# S5D3_MCU_only.net
KiCad netlist of a schematic drawn in EAGLE
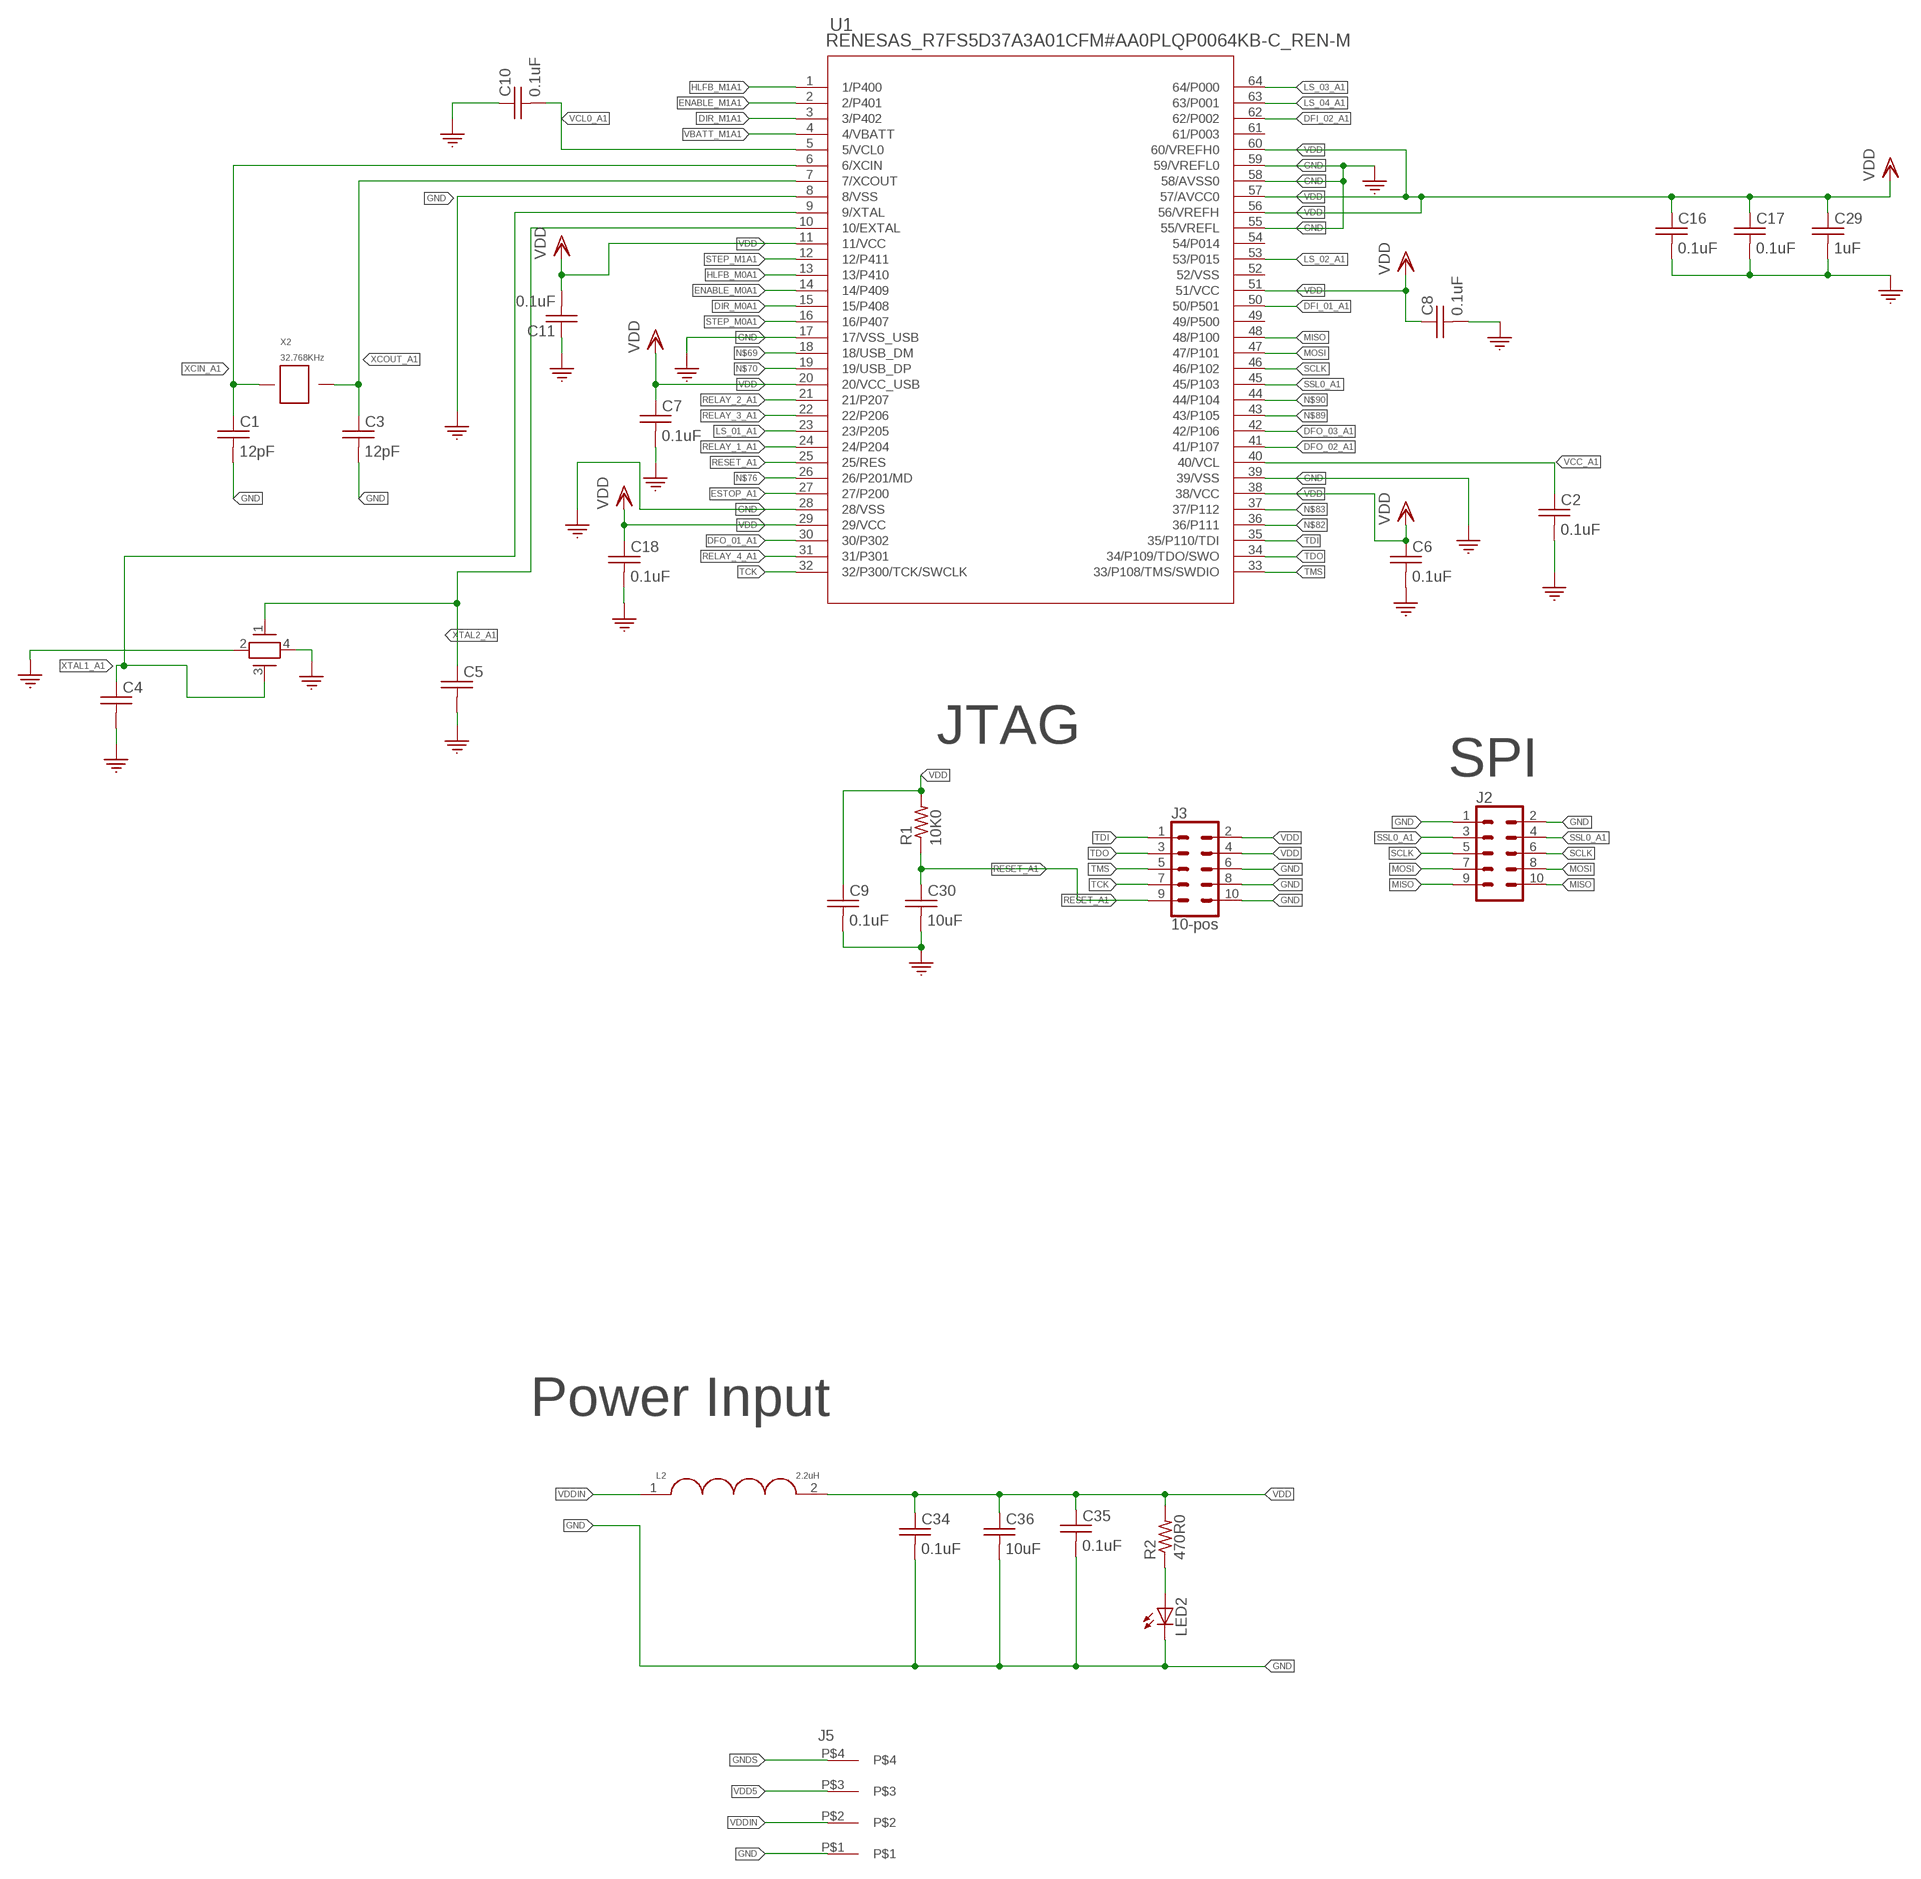
[diagram p0: schematic, sheet 1]

(export (version "E")
  (design (tool "Eeschema 10.0.6"))
  (components
    (comp (ref "C1")
      (value "12pF")
      (footprint "eagle-import:0402")
      (fields (field (name "PARTNO") "CL05C120JB5NNNC"))
      (libsource (lib "eagle-import") (part "C_0402_12PF"))
    )
    (comp (ref "C2")
      (value "0.1uF")
      (footprint "eagle-import:0402")
      (fields (field (name "PARTNO") "CL05F104ZO5NNNC"))
      (libsource (lib "eagle-import") (part "C_0402_0.1UF"))
    )
    (comp (ref "C3")
      (value "12pF")
      (footprint "eagle-import:0402")
      (fields (field (name "PARTNO") "CL05C120JB5NNNC"))
      (libsource (lib "eagle-import") (part "C_0402_12PF"))
    )
    (comp (ref "C4")
      (value "10pF")
      (footprint "eagle-import:0402")
      (fields (field (name "PARTNO") "CC0402JRNPO9BN100"))
      (libsource (lib "eagle-import") (part "C_0402_10PF"))
    )
    (comp (ref "C5")
      (value "10pF")
      (footprint "eagle-import:0402")
      (fields (field (name "PARTNO") "CC0402JRNPO9BN100"))
      (libsource (lib "eagle-import") (part "C_0402_10PF"))
    )
    (comp (ref "C6")
      (value "0.1uF")
      (footprint "eagle-import:0402")
      (fields (field (name "PARTNO") "CL05F104ZO5NNNC"))
      (libsource (lib "eagle-import") (part "C_0402_0.1UF"))
    )
    (comp (ref "C7")
      (value "0.1uF")
      (footprint "eagle-import:0402")
      (fields (field (name "PARTNO") "CL05F104ZO5NNNC"))
      (libsource (lib "eagle-import") (part "C_0402_0.1UF"))
    )
    (comp (ref "C8")
      (value "0.1uF")
      (footprint "eagle-import:0402")
      (fields (field (name "PARTNO") "CL05F104ZO5NNNC"))
      (libsource (lib "eagle-import") (part "C_0402_0.1UF"))
    )
    (comp (ref "C9")
      (value "0.1uF")
      (footprint "eagle-import:0402")
      (fields (field (name "PARTNO") "CL05F104ZO5NNNC"))
      (libsource (lib "eagle-import") (part "C_0402_0.1UF"))
    )
    (comp (ref "C10")
      (value "0.1uF")
      (footprint "eagle-import:0402")
      (fields (field (name "PARTNO") "CL05F104ZO5NNNC"))
      (libsource (lib "eagle-import") (part "C_0402_0.1UF"))
    )
    (comp (ref "C11")
      (value "0.1uF")
      (footprint "eagle-import:0402")
      (fields (field (name "PARTNO") "CL05F104ZO5NNNC"))
      (libsource (lib "eagle-import") (part "C_0402_0.1UF"))
    )
    (comp (ref "C16")
      (value "0.1uF")
      (footprint "eagle-import:0402")
      (fields (field (name "PARTNO") "CL05F104ZO5NNNC"))
      (libsource (lib "eagle-import") (part "C_0402_0.1UF"))
    )
    (comp (ref "C17")
      (value "0.1uF")
      (footprint "eagle-import:0402")
      (fields (field (name "PARTNO") "CL05F104ZO5NNNC"))
      (libsource (lib "eagle-import") (part "C_0402_0.1UF"))
    )
    (comp (ref "C18")
      (value "0.1uF")
      (footprint "eagle-import:0402")
      (fields (field (name "PARTNO") "CL05F104ZO5NNNC"))
      (libsource (lib "eagle-import") (part "C_0402_0.1UF"))
    )
    (comp (ref "C29")
      (value "1uF")
      (footprint "eagle-import:0402")
      (fields (field (name "PARTNO") "CL05A105KO5NNNC"))
      (libsource (lib "eagle-import") (part "C_0402_1UF"))
    )
    (comp (ref "C30")
      (value "10uF")
      (footprint "eagle-import:0402")
      (fields (field (name "PARTNO") "CL05A106MP8NUB8"))
      (libsource (lib "eagle-import") (part "C_0402_10UF"))
    )
    (comp (ref "C34")
      (value "0.1uF")
      (footprint "eagle-import:0402")
      (fields (field (name "PARTNO") "CL05F104ZO5NNNC"))
      (libsource (lib "eagle-import") (part "C_0402_0.1UF"))
    )
    (comp (ref "C35")
      (value "0.1uF")
      (footprint "eagle-import:0402")
      (fields (field (name "PARTNO") "CL05F104ZO5NNNC"))
      (libsource (lib "eagle-import") (part "C_0402_0.1UF"))
    )
    (comp (ref "C36")
      (value "10uF")
      (footprint "eagle-import:0402")
      (fields (field (name "PARTNO") "CL05A106MP8NUB8"))
      (libsource (lib "eagle-import") (part "C_0402_10UF"))
    )
    (comp (ref "J2")
      (value "CONN_05X2PTH")
      (footprint "eagle-import:2X5")
      (libsource (lib "eagle-import") (part "CONN_05X2PTH"))
    )
    (comp (ref "J3")
      (value "10-pos")
      (footprint "eagle-import:2X5")
      (fields (field (name "PARTNO") "PH2RA-10-UA"))
      (libsource (lib "eagle-import") (part "CONN_05X2_RAPTH"))
    )
    (comp (ref "J5")
      (value "4-pos")
      (footprint "eagle-import:1X4_3.81MM_PITCH")
      (fields (field (name "PARTNO") "691322310004"))
      (libsource (lib "eagle-import") (part "3.81MM_1_X_4_RT_ANGLE_PLUG_HEADER"))
    )
    (comp (ref "L2")
      (value "2.2uH")
      (footprint "eagle-import:1008")
      (fields (field (name "PARTNO") "LQM2HPN2R2MG0L"))
      (libsource (lib "eagle-import") (part "INDUCTOR_1008_2.2_MH_1.3A"))
    )
    (comp (ref "LED2")
      (value "Green")
      (footprint "eagle-import:0805")
      (fields (field (name "PARTNO") "LG R971-KN-1"))
      (libsource (lib "eagle-import") (part "LED_0805_GREEN"))
    )
    (comp (ref "R1")
      (value "10K0")
      (footprint "eagle-import:0402")
      (fields (field (name "PARTNO") "RMCF0402JT10K0"))
      (libsource (lib "eagle-import") (part "R_0402_10K0"))
    )
    (comp (ref "R2")
      (value "470R0")
      (footprint "eagle-import:0402")
      (fields (field (name "PARTNO") "RMCF0402JT470R"))
      (libsource (lib "eagle-import") (part "R_0402_470R0"))
    )
    (comp (ref "U1")
      (value "RENESAS_R7FS5D37A3A01CFM#AA0PLQP0064KB-C_REN-M")
      (footprint "eagle-import:PLQP0064KB-C_REN-M")
      (fields
        (field (name "PARTNO") "R7FS3A37A3A01CFM#AA0")
        (field (name "COPYRIGHT") "Copyright (C) 2023 Ultra Librarian. All rights reserved.")
      )
      (libsource (lib "eagle-import") (part "RENESAS_R7FS5D37A3A01CFM#AA0PLQP0064KB-C_REN-M"))
    )
    (comp (ref "X2")
      (value "32.768KHz")
      (footprint "eagle-import:SMD_X_2_PADS")
      (fields (field (name "PARTNO") "ABS07-32.768KHZ-T"))
      (libsource (lib "eagle-import") (part "XTAL_32.768KHZ"))
    )
    (comp (ref "Y1")
      (value "XTAL_12MHZ_ABM8G-12.000MHZ-B4Y-T")
      (footprint "eagle-import:CRYSTAL_ABM8G_ABR")
      (fields
        (field (name "PARTNO") "ABM8G-12.000MHZ-B4Y-T")
        (field (name "COPYRIGHT") "Copyright (C) 2023 Ultra Librarian. All rights reserved.")
      )
      (libsource (lib "eagle-import") (part "XTAL_12MHZ_ABM8G-12.000MHZ-B4Y-T"))
    )
  )
  (nets
    (net (code "1") (name "DFI_01_A1") (class "Default")
      (node (ref "U1") (pin "50") (pinfunction "50/P501_50") (pintype "bidirectional"))
    )
    (net (code "2") (name "DFI_02_A1") (class "Default")
      (node (ref "U1") (pin "62") (pinfunction "62/P002_62") (pintype "bidirectional"))
    )
    (net (code "3") (name "DFO_01_A1") (class "Default")
      (node (ref "U1") (pin "30") (pinfunction "30/P302_30") (pintype "bidirectional"))
    )
    (net (code "4") (name "DFO_02_A1") (class "Default")
      (node (ref "U1") (pin "41") (pinfunction "41/P107_41") (pintype "bidirectional"))
    )
    (net (code "5") (name "DFO_03_A1") (class "Default")
      (node (ref "U1") (pin "42") (pinfunction "42/P106_42") (pintype "bidirectional"))
    )
    (net (code "6") (name "DIR_M0A1") (class "Default")
      (node (ref "U1") (pin "15") (pinfunction "15/P408_15") (pintype "bidirectional"))
    )
    (net (code "7") (name "DIR_M1A1") (class "Default")
      (node (ref "U1") (pin "3") (pinfunction "3/P402_3") (pintype "bidirectional"))
    )
    (net (code "8") (name "ENABLE_M0A1") (class "Default")
      (node (ref "U1") (pin "14") (pinfunction "14/P409_14") (pintype "bidirectional"))
    )
    (net (code "9") (name "ENABLE_M1A1") (class "Default")
      (node (ref "U1") (pin "2") (pinfunction "2/P401_2") (pintype "bidirectional"))
    )
    (net (code "10") (name "ESTOP_A1") (class "Default")
      (node (ref "U1") (pin "27") (pinfunction "27/P200_27") (pintype "bidirectional"))
    )
    (net (code "11") (name "GND") (class "Default")
      (node (ref "C1") (pin "P$2") (pinfunction "2_P$2") (pintype "passive"))
      (node (ref "C10") (pin "P$1") (pinfunction "1_P$1") (pintype "passive"))
      (node (ref "C11") (pin "P$1") (pinfunction "1_P$1") (pintype "passive"))
      (node (ref "C16") (pin "P$2") (pinfunction "2_P$2") (pintype "passive"))
      (node (ref "C17") (pin "P$2") (pinfunction "2_P$2") (pintype "passive"))
      (node (ref "C18") (pin "P$2") (pinfunction "2_P$2") (pintype "passive"))
      (node (ref "C2") (pin "P$2") (pinfunction "2_P$2") (pintype "passive"))
      (node (ref "C29") (pin "P$2") (pinfunction "2_P$2") (pintype "passive"))
      (node (ref "C3") (pin "P$2") (pinfunction "2_P$2") (pintype "passive"))
      (node (ref "C30") (pin "P$2") (pinfunction "2_P$2") (pintype "passive"))
      (node (ref "C34") (pin "P$2") (pinfunction "2_P$2") (pintype "passive"))
      (node (ref "C35") (pin "P$2") (pinfunction "2_P$2") (pintype "passive"))
      (node (ref "C36") (pin "P$2") (pinfunction "2_P$2") (pintype "passive"))
      (node (ref "C4") (pin "P$2") (pinfunction "2_P$2") (pintype "passive"))
      (node (ref "C5") (pin "P$2") (pinfunction "2_P$2") (pintype "passive"))
      (node (ref "C6") (pin "P$2") (pinfunction "2_P$2") (pintype "passive"))
      (node (ref "C7") (pin "P$2") (pinfunction "2_P$2") (pintype "passive"))
      (node (ref "C8") (pin "P$2") (pinfunction "2_P$2") (pintype "passive"))
      (node (ref "C9") (pin "P$2") (pinfunction "2_P$2") (pintype "passive"))
      (node (ref "J2") (pin "1") (pinfunction "1_1") (pintype "passive"))
      (node (ref "J2") (pin "2") (pinfunction "2_2") (pintype "passive"))
      (node (ref "J3") (pin "10") (pinfunction "10_10") (pintype "passive"))
      (node (ref "J3") (pin "6") (pinfunction "6_6") (pintype "passive"))
      (node (ref "J3") (pin "8") (pinfunction "8_8") (pintype "passive"))
      (node (ref "J5") (pin "P$1") (pinfunction "P$1_P$1") (pintype "bidirectional"))
      (node (ref "LED2") (pin "2") (pinfunction "C_2") (pintype "passive"))
      (node (ref "U1") (pin "17") (pinfunction "17/VSS_USB_17") (pintype "power_in"))
      (node (ref "U1") (pin "28") (pinfunction "28/VSS_28") (pintype "bidirectional"))
      (node (ref "U1") (pin "39") (pinfunction "39/VSS_39") (pintype "power_in"))
      (node (ref "U1") (pin "55") (pinfunction "55/VREFL_55") (pintype "bidirectional"))
      (node (ref "U1") (pin "58") (pinfunction "58/AVSS0_58") (pintype "bidirectional"))
      (node (ref "U1") (pin "59") (pinfunction "59/VREFL0_59") (pintype "bidirectional"))
      (node (ref "U1") (pin "8") (pinfunction "8/VSS_8") (pintype "power_in"))
      (node (ref "Y1") (pin "2") (pinfunction "2_2") (pintype "passive"))
      (node (ref "Y1") (pin "4") (pinfunction "4_4") (pintype "passive"))
    )
    (net (code "12") (name "GNDS") (class "Default")
      (node (ref "J5") (pin "P$4") (pinfunction "P$4_P$4") (pintype "bidirectional"))
    )
    (net (code "13") (name "HLFB_M0A1") (class "Default")
      (node (ref "U1") (pin "13") (pinfunction "13/P410_13") (pintype "bidirectional"))
    )
    (net (code "14") (name "HLFB_M1A1") (class "Default")
      (node (ref "U1") (pin "1") (pinfunction "1/P400_1") (pintype "bidirectional"))
    )
    (net (code "15") (name "LS_01_A1") (class "Default")
      (node (ref "U1") (pin "23") (pinfunction "23/P205_23") (pintype "bidirectional"))
    )
    (net (code "16") (name "LS_02_A1") (class "Default")
      (node (ref "U1") (pin "53") (pinfunction "53/P015_53") (pintype "bidirectional"))
    )
    (net (code "17") (name "LS_03_A1") (class "Default")
      (node (ref "U1") (pin "64") (pinfunction "64/P000_64") (pintype "bidirectional"))
    )
    (net (code "18") (name "LS_04_A1") (class "Default")
      (node (ref "U1") (pin "63") (pinfunction "63/P001_63") (pintype "bidirectional"))
    )
    (net (code "19") (name "MISO") (class "Default")
      (node (ref "J2") (pin "10") (pinfunction "10_10") (pintype "passive"))
      (node (ref "J2") (pin "9") (pinfunction "9_9") (pintype "passive"))
      (node (ref "U1") (pin "48") (pinfunction "48/P100_48") (pintype "bidirectional"))
    )
    (net (code "20") (name "MOSI") (class "Default")
      (node (ref "J2") (pin "7") (pinfunction "7_7") (pintype "passive"))
      (node (ref "J2") (pin "8") (pinfunction "8_8") (pintype "passive"))
      (node (ref "U1") (pin "47") (pinfunction "47/P101_47") (pintype "bidirectional"))
    )
    (net (code "21") (name "N$69") (class "Default")
      (node (ref "U1") (pin "18") (pinfunction "18/USB_DM_18") (pintype "bidirectional"))
    )
    (net (code "22") (name "N$70") (class "Default")
      (node (ref "U1") (pin "19") (pinfunction "19/USB_DP_19") (pintype "bidirectional"))
    )
    (net (code "23") (name "N$76") (class "Default")
      (node (ref "U1") (pin "26") (pinfunction "26/P201/MD_26") (pintype "bidirectional"))
    )
    (net (code "24") (name "N$82") (class "Default")
      (node (ref "U1") (pin "36") (pinfunction "36/P111_36") (pintype "bidirectional"))
    )
    (net (code "25") (name "N$83") (class "Default")
      (node (ref "U1") (pin "37") (pinfunction "37/P112_37") (pintype "bidirectional"))
    )
    (net (code "26") (name "N$89") (class "Default")
      (node (ref "U1") (pin "43") (pinfunction "43/P105_43") (pintype "bidirectional"))
    )
    (net (code "27") (name "N$90") (class "Default")
      (node (ref "U1") (pin "44") (pinfunction "44/P104_44") (pintype "bidirectional"))
    )
    (net (code "28") (name "Net-(LED2-A)") (class "Default")
      (node (ref "LED2") (pin "1") (pinfunction "A_1") (pintype "passive"))
      (node (ref "R2") (pin "P$1") (pinfunction "1_P$1") (pintype "passive"))
    )
    (net (code "29") (name "RELAY_1_A1") (class "Default")
      (node (ref "U1") (pin "24") (pinfunction "24/P204_24") (pintype "bidirectional"))
    )
    (net (code "30") (name "RELAY_2_A1") (class "Default")
      (node (ref "U1") (pin "21") (pinfunction "21/P207_21") (pintype "power_in"))
    )
    (net (code "31") (name "RELAY_3_A1") (class "Default")
      (node (ref "U1") (pin "22") (pinfunction "22/P206_22") (pintype "bidirectional"))
    )
    (net (code "32") (name "RELAY_4_A1") (class "Default")
      (node (ref "U1") (pin "31") (pinfunction "31/P301_31") (pintype "bidirectional"))
    )
    (net (code "33") (name "RESET_A1") (class "Default")
      (node (ref "C30") (pin "P$1") (pinfunction "1_P$1") (pintype "passive"))
      (node (ref "J3") (pin "9") (pinfunction "9_9") (pintype "passive"))
      (node (ref "R1") (pin "P$1") (pinfunction "1_P$1") (pintype "passive"))
      (node (ref "U1") (pin "25") (pinfunction "25/RES_25") (pintype "input"))
    )
    (net (code "34") (name "SCLK") (class "Default")
      (node (ref "J2") (pin "5") (pinfunction "5_5") (pintype "passive"))
      (node (ref "J2") (pin "6") (pinfunction "6_6") (pintype "passive"))
      (node (ref "U1") (pin "46") (pinfunction "46/P102_46") (pintype "bidirectional"))
    )
    (net (code "35") (name "SSL0_A1") (class "Default")
      (node (ref "J2") (pin "3") (pinfunction "3_3") (pintype "passive"))
      (node (ref "J2") (pin "4") (pinfunction "4_4") (pintype "passive"))
      (node (ref "U1") (pin "45") (pinfunction "45/P103_45") (pintype "bidirectional"))
    )
    (net (code "36") (name "STEP_M0A1") (class "Default")
      (node (ref "U1") (pin "16") (pinfunction "16/P407_16") (pintype "bidirectional"))
    )
    (net (code "37") (name "STEP_M1A1") (class "Default")
      (node (ref "U1") (pin "12") (pinfunction "12/P411_12") (pintype "bidirectional"))
    )
    (net (code "38") (name "TCK") (class "Default")
      (node (ref "J3") (pin "7") (pinfunction "7_7") (pintype "passive"))
      (node (ref "U1") (pin "32") (pinfunction "32/P300/TCK/SWCLK_32") (pintype "bidirectional"))
    )
    (net (code "39") (name "TDI") (class "Default")
      (node (ref "J3") (pin "1") (pinfunction "1_1") (pintype "passive"))
      (node (ref "U1") (pin "35") (pinfunction "35/P110/TDI_35") (pintype "bidirectional"))
    )
    (net (code "40") (name "TDO") (class "Default")
      (node (ref "J3") (pin "3") (pinfunction "3_3") (pintype "passive"))
      (node (ref "U1") (pin "34") (pinfunction "34/P109/TDO/SWO_34") (pintype "bidirectional"))
    )
    (net (code "41") (name "TMS") (class "Default")
      (node (ref "J3") (pin "5") (pinfunction "5_5") (pintype "passive"))
      (node (ref "U1") (pin "33") (pinfunction "33/P108/TMS/SWDIO_33") (pintype "bidirectional"))
    )
    (net (code "42") (name "VBATT_M1A1") (class "Default")
      (node (ref "U1") (pin "4") (pinfunction "4/VBATT_4") (pintype "power_in"))
    )
    (net (code "43") (name "VCC_A1") (class "Default")
      (node (ref "C2") (pin "P$1") (pinfunction "1_P$1") (pintype "passive"))
      (node (ref "U1") (pin "40") (pinfunction "40/VCL_40") (pintype "power_in"))
    )
    (net (code "44") (name "VCL0_A1") (class "Default")
      (node (ref "C10") (pin "P$2") (pinfunction "2_P$2") (pintype "passive"))
      (node (ref "U1") (pin "5") (pinfunction "5/VCL0_5") (pintype "power_in"))
    )
    (net (code "45") (name "VDD") (class "Default")
      (node (ref "C11") (pin "P$2") (pinfunction "2_P$2") (pintype "passive"))
      (node (ref "C16") (pin "P$1") (pinfunction "1_P$1") (pintype "passive"))
      (node (ref "C17") (pin "P$1") (pinfunction "1_P$1") (pintype "passive"))
      (node (ref "C18") (pin "P$1") (pinfunction "1_P$1") (pintype "passive"))
      (node (ref "C29") (pin "P$1") (pinfunction "1_P$1") (pintype "passive"))
      (node (ref "C34") (pin "P$1") (pinfunction "1_P$1") (pintype "passive"))
      (node (ref "C35") (pin "P$1") (pinfunction "1_P$1") (pintype "passive"))
      (node (ref "C36") (pin "P$1") (pinfunction "1_P$1") (pintype "passive"))
      (node (ref "C6") (pin "P$1") (pinfunction "1_P$1") (pintype "passive"))
      (node (ref "C7") (pin "P$1") (pinfunction "1_P$1") (pintype "passive"))
      (node (ref "C8") (pin "P$1") (pinfunction "1_P$1") (pintype "passive"))
      (node (ref "C9") (pin "P$1") (pinfunction "1_P$1") (pintype "passive"))
      (node (ref "J3") (pin "2") (pinfunction "2_2") (pintype "passive"))
      (node (ref "J3") (pin "4") (pinfunction "4_4") (pintype "passive"))
      (node (ref "L2") (pin "2") (pinfunction "P$2_2") (pintype "bidirectional"))
      (node (ref "R1") (pin "P$2") (pinfunction "2_P$2") (pintype "passive"))
      (node (ref "R2") (pin "P$2") (pinfunction "2_P$2") (pintype "passive"))
      (node (ref "U1") (pin "11") (pinfunction "11/VCC_11") (pintype "power_in"))
      (node (ref "U1") (pin "20") (pinfunction "20/VCC_USB_20") (pintype "power_in"))
      (node (ref "U1") (pin "29") (pinfunction "29/VCC_29") (pintype "bidirectional"))
      (node (ref "U1") (pin "38") (pinfunction "38/VCC_38") (pintype "bidirectional"))
      (node (ref "U1") (pin "51") (pinfunction "51/VCC_51") (pintype "bidirectional"))
      (node (ref "U1") (pin "56") (pinfunction "56/VREFH_56") (pintype "power_in"))
      (node (ref "U1") (pin "57") (pinfunction "57/AVCC0_57") (pintype "power_in"))
      (node (ref "U1") (pin "60") (pinfunction "60/VREFH0_60") (pintype "bidirectional"))
    )
    (net (code "46") (name "VDD5") (class "Default")
      (node (ref "J5") (pin "P$3") (pinfunction "P$3_P$3") (pintype "bidirectional"))
    )
    (net (code "47") (name "VDDIN") (class "Default")
      (node (ref "J5") (pin "P$2") (pinfunction "P$2_P$2") (pintype "bidirectional"))
      (node (ref "L2") (pin "1") (pinfunction "P$1_1") (pintype "bidirectional"))
    )
    (net (code "48") (name "XCIN_A1") (class "Default")
      (node (ref "C1") (pin "P$1") (pinfunction "1_P$1") (pintype "passive"))
      (node (ref "U1") (pin "6") (pinfunction "6/XCIN_6") (pintype "bidirectional"))
      (node (ref "X2") (pin "P$1") (pinfunction "P$1_P$1") (pintype "bidirectional"))
    )
    (net (code "49") (name "XCOUT_A1") (class "Default")
      (node (ref "C3") (pin "P$1") (pinfunction "1_P$1") (pintype "passive"))
      (node (ref "U1") (pin "7") (pinfunction "7/XCOUT_7") (pintype "bidirectional"))
      (node (ref "X2") (pin "P$2") (pinfunction "P$2_P$2") (pintype "bidirectional"))
    )
    (net (code "50") (name "XTAL1_A1") (class "Default")
      (node (ref "C4") (pin "P$1") (pinfunction "1_P$1") (pintype "passive"))
      (node (ref "U1") (pin "9") (pinfunction "9/XTAL_9") (pintype "bidirectional"))
      (node (ref "Y1") (pin "3") (pinfunction "3_3") (pintype "passive"))
    )
    (net (code "51") (name "XTAL2_A1") (class "Default")
      (node (ref "C5") (pin "P$1") (pinfunction "1_P$1") (pintype "passive"))
      (node (ref "U1") (pin "10") (pinfunction "10/EXTAL_10") (pintype "bidirectional"))
      (node (ref "Y1") (pin "1") (pinfunction "1_1") (pintype "passive"))
    )
    (net (code "52") (name "unconnected-(U1-49{slash}P500-Pad49)") (class "Default")
      (node (ref "U1") (pin "49") (pinfunction "49/P500_49") (pintype "bidirectional"))
    )
    (net (code "53") (name "unconnected-(U1-52{slash}VSS-Pad52)") (class "Default")
      (node (ref "U1") (pin "52") (pinfunction "52/VSS_52") (pintype "bidirectional"))
    )
    (net (code "54") (name "unconnected-(U1-54{slash}P014-Pad54)") (class "Default")
      (node (ref "U1") (pin "54") (pinfunction "54/P014_54") (pintype "bidirectional"))
    )
    (net (code "55") (name "unconnected-(U1-61{slash}P003-Pad61)") (class "Default")
      (node (ref "U1") (pin "61") (pinfunction "61/P003_61") (pintype "bidirectional"))
    )
  )
)
